# MINI_SAM_D51_009.net
KiCad netlist of a schematic drawn in EAGLE
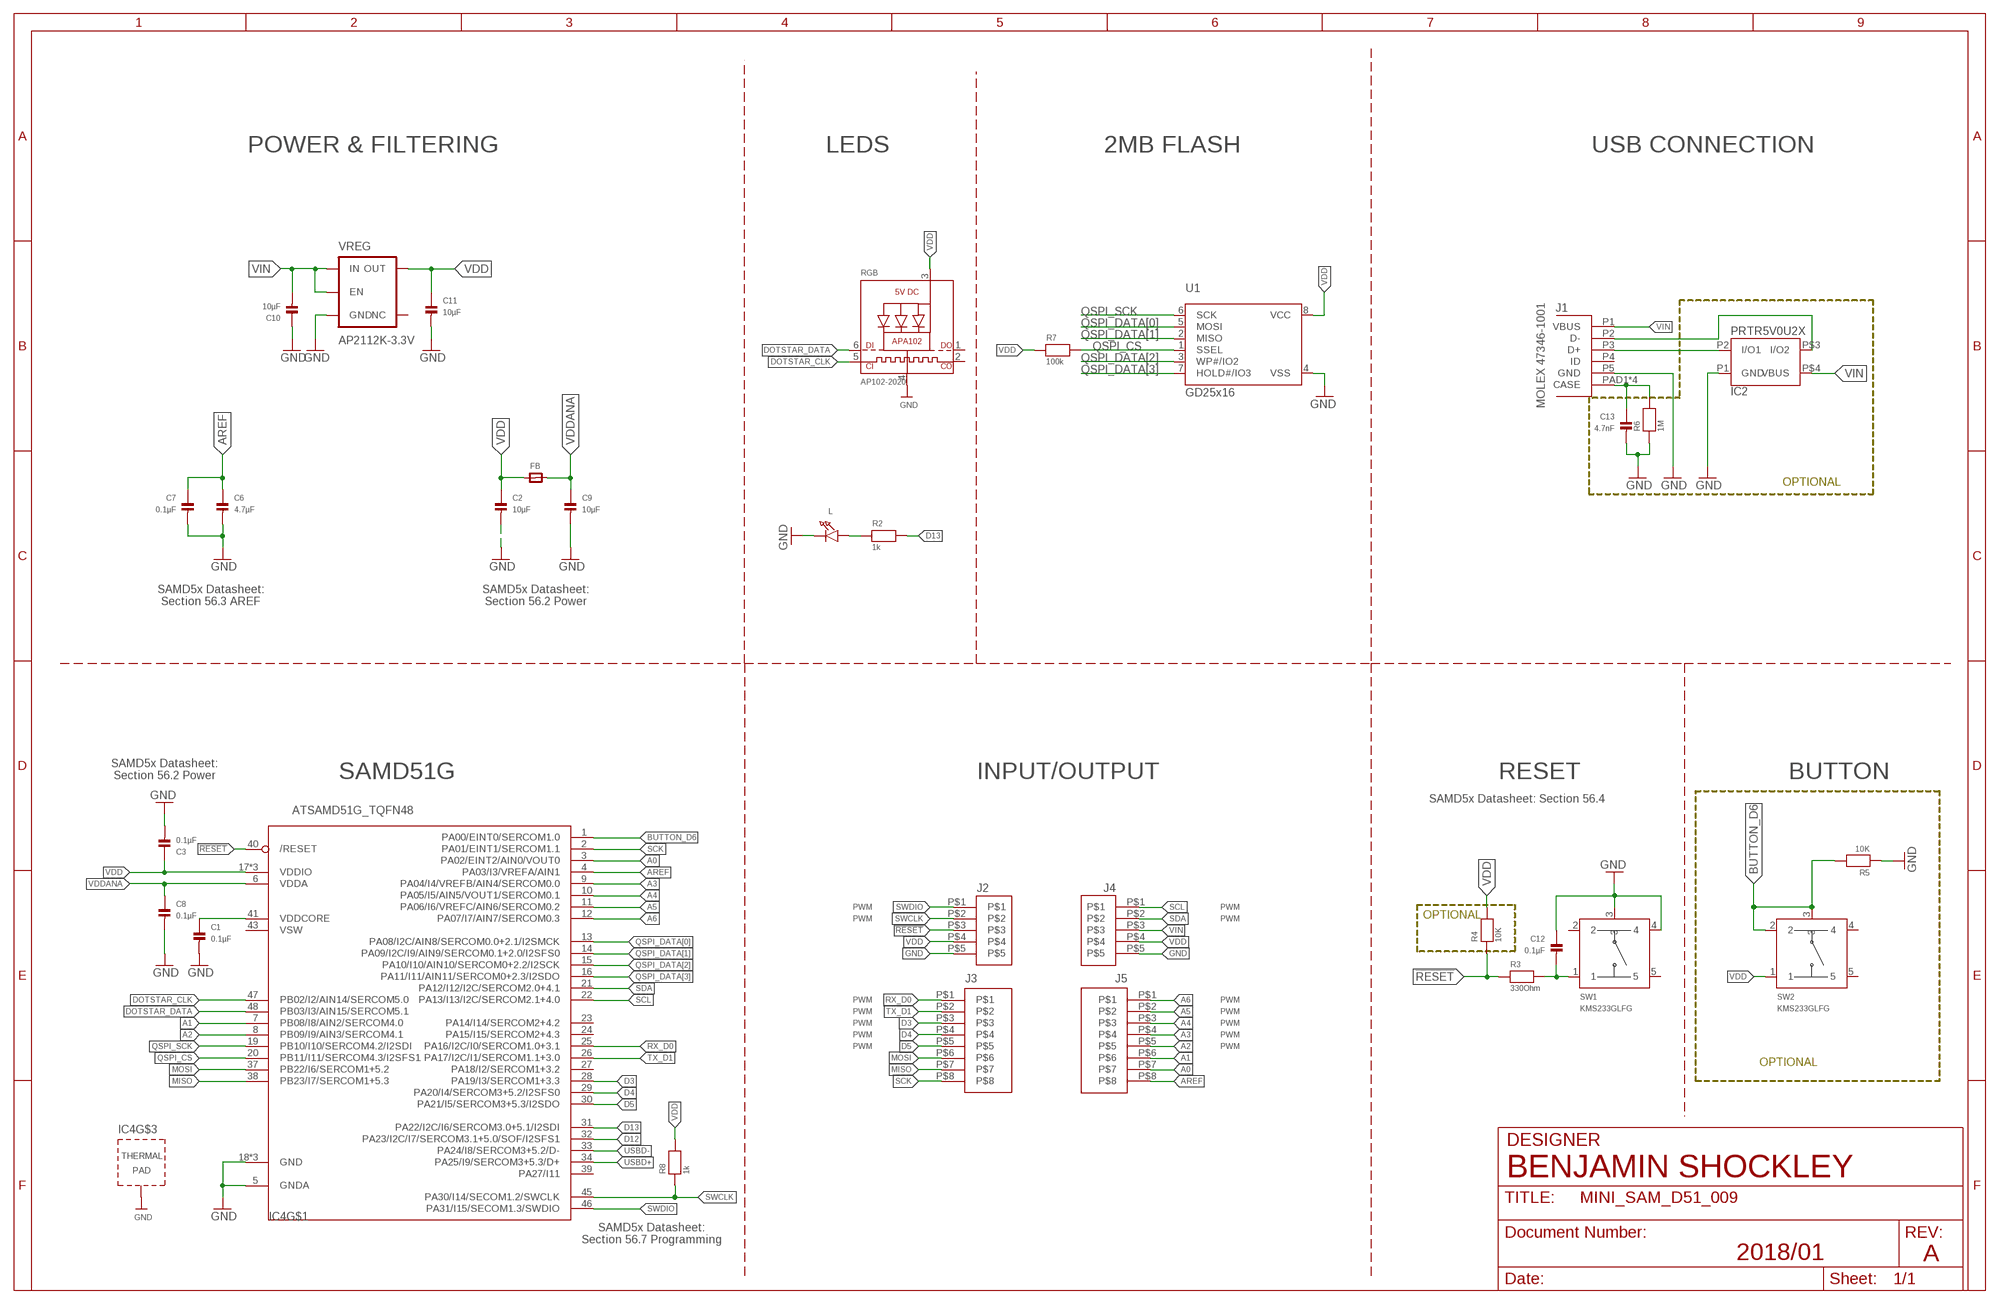
[diagram p0: schematic, sheet 1]

(export (version "E")
  (design (tool "Eeschema 10.0.6"))
  (components
    (comp (ref "C1")
      (value "0.1µF")
      (footprint "eagle-import:_0603MP")
      (libsource (lib "eagle-import") (part "CAP_CERAMIC_0603MP"))
    )
    (comp (ref "C2")
      (value "10µF")
      (footprint "eagle-import:_0603MP")
      (libsource (lib "eagle-import") (part "CAP_CERAMIC_0603MP"))
    )
    (comp (ref "C3")
      (value "0.1µF")
      (footprint "eagle-import:_0603MP")
      (libsource (lib "eagle-import") (part "CAP_CERAMIC_0603MP"))
    )
    (comp (ref "C6")
      (value "4.7µF")
      (footprint "eagle-import:_0603MP")
      (libsource (lib "eagle-import") (part "CAP_CERAMIC_0603MP"))
    )
    (comp (ref "C7")
      (value "0.1µF")
      (footprint "eagle-import:_0603MP")
      (libsource (lib "eagle-import") (part "CAP_CERAMIC_0603MP"))
    )
    (comp (ref "C8")
      (value "0.1µF")
      (footprint "eagle-import:_0603MP")
      (libsource (lib "eagle-import") (part "CAP_CERAMIC_0603MP"))
    )
    (comp (ref "C9")
      (value "10µF")
      (footprint "eagle-import:_0603MP")
      (libsource (lib "eagle-import") (part "CAP_CERAMIC_0603MP"))
    )
    (comp (ref "C10")
      (value "10µF")
      (footprint "eagle-import:_0603MP")
      (libsource (lib "eagle-import") (part "CAP_CERAMIC_0603MP"))
    )
    (comp (ref "C11")
      (value "10µF")
      (footprint "eagle-import:_0603MP")
      (libsource (lib "eagle-import") (part "CAP_CERAMIC_0603MP"))
    )
    (comp (ref "C12")
      (value "0.1µF")
      (footprint "eagle-import:_0603MP")
      (libsource (lib "eagle-import") (part "CAP_CERAMIC_0603MP"))
    )
    (comp (ref "C13")
      (value "4.7nF")
      (footprint "eagle-import:_0603MP")
      (libsource (lib "eagle-import") (part "CAP_CERAMIC_0603MP"))
    )
    (comp (ref "FB")
      (value "FERRITE_0603MP")
      (footprint "eagle-import:_0603MP")
      (libsource (lib "eagle-import") (part "FERRITE_0603MP"))
    )
    (comp (ref "IC2")
      (value "PRTR5V0U2X")
      (footprint "eagle-import:SOT143B_REFLOW")
      (libsource (lib "eagle-import") (part "PRTR5V0U2X"))
    )
    (comp (ref "IC4")
      (value "ATSAMD51G_TQFN48")
      (footprint "eagle-import:TQFN48_7MM")
      (libsource (lib "eagle-import") (part "ATSAMD51G_TQFN48"))
    )
    (comp (ref "J1")
      (value "MOLEX_47346-100147346")
      (footprint "eagle-import:MOLEX_47346-1001")
      (libsource (lib "eagle-import") (part "MOLEX_47346-100147346"))
    )
    (comp (ref "J2")
      (value "1X5_HEADER_1.27MM")
      (footprint "eagle-import:1X5_HEADER_1.27MM")
      (libsource (lib "eagle-import") (part "1X5_HEADER_1.27MM"))
    )
    (comp (ref "J3")
      (value "1X8_HEADER_1.27MM")
      (footprint "eagle-import:1X8_HEADER_1.27MM")
      (libsource (lib "eagle-import") (part "1X8_HEADER_1.27MM"))
    )
    (comp (ref "J4")
      (value "1X5_HEADER_1.27MM")
      (footprint "eagle-import:1X5_HEADER_1.27MM")
      (libsource (lib "eagle-import") (part "1X5_HEADER_1.27MM"))
    )
    (comp (ref "J5")
      (value "1X8_HEADER_1.27MM")
      (footprint "eagle-import:1X8_HEADER_1.27MM")
      (libsource (lib "eagle-import") (part "1X8_HEADER_1.27MM"))
    )
    (comp (ref "L")
      (value "LED0603_NOOUTLINE")
      (footprint "eagle-import:CHIPLED_0603_NOOUTLINE")
      (libsource (lib "eagle-import") (part "LED0603_NOOUTLINE"))
    )
    (comp (ref "R2")
      (value "1k")
      (footprint "eagle-import:_0603MP")
      (libsource (lib "eagle-import") (part "RESISTOR_0603MP"))
    )
    (comp (ref "R3")
      (value "330Ohm")
      (footprint "eagle-import:_0603MP")
      (libsource (lib "eagle-import") (part "RESISTOR_0603MP"))
    )
    (comp (ref "R4")
      (value "10K")
      (footprint "eagle-import:_0603MP")
      (libsource (lib "eagle-import") (part "RESISTOR_0603MP"))
    )
    (comp (ref "R5")
      (value "10K")
      (footprint "eagle-import:_0603MP")
      (libsource (lib "eagle-import") (part "RESISTOR_0603MP"))
    )
    (comp (ref "R6")
      (value "1M")
      (footprint "eagle-import:_0603MP")
      (libsource (lib "eagle-import") (part "RESISTOR_0603MP"))
    )
    (comp (ref "R7")
      (value "100k")
      (footprint "eagle-import:_0603MP")
      (libsource (lib "eagle-import") (part "RESISTOR_0603MP"))
    )
    (comp (ref "R8")
      (value "1k")
      (footprint "eagle-import:_0603MP")
      (libsource (lib "eagle-import") (part "RESISTOR_0603MP"))
    )
    (comp (ref "RGB")
      (value "AP102-2020")
      (footprint "eagle-import:APA102_2020")
      (libsource (lib "eagle-import") (part "APA1022020"))
    )
    (comp (ref "SW1")
      (value "KMS233GLFG")
      (footprint "eagle-import:KMS_SWITCH")
      (libsource (lib "eagle-import") (part "KMS_SWITCHKMS"))
    )
    (comp (ref "SW2")
      (value "KMS233GLFG")
      (footprint "eagle-import:KMS_SWITCH")
      (libsource (lib "eagle-import") (part "KMS_SWITCHKMS"))
    )
    (comp (ref "U1")
      (value "GD25x16")
      (footprint "eagle-import:USON8")
      (libsource (lib "eagle-import") (part "SPIFLASH_8PINUX"))
    )
    (comp (ref "VREG")
      (value "AP2112K-3.3V")
      (footprint "eagle-import:SOT23-5")
      (libsource (lib "eagle-import") (part "V_REG_AP2112K-3.3V"))
    )
  )
  (nets
    (net (code "1") (name "/VSW") (class "Default")
      (node (ref "IC4") (pin "43") (pinfunction "VSW_43") (pintype "power_in"))
    )
    (net (code "2") (name "/~{RESET}") (class "Default")
      (node (ref "IC4") (pin "40") (pinfunction "/RESET_40") (pintype "bidirectional"))
      (node (ref "J2") (pin "P$3") (pinfunction "P$3_P$3") (pintype "bidirectional"))
      (node (ref "R3") (pin "1") (pinfunction "1_1") (pintype "passive"))
      (node (ref "R4") (pin "1") (pinfunction "1_1") (pintype "passive"))
    )
    (net (code "3") (name "A0") (class "Default")
      (node (ref "IC4") (pin "3") (pinfunction "PA02/EINT2/AIN0/VOUT0_3") (pintype "bidirectional"))
      (node (ref "J5") (pin "P$7") (pinfunction "P$7_P$7") (pintype "bidirectional"))
    )
    (net (code "4") (name "A1") (class "Default")
      (node (ref "IC4") (pin "7") (pinfunction "PB08/I8/AIN2/SERCOM4.0_7") (pintype "bidirectional"))
      (node (ref "J5") (pin "P$6") (pinfunction "P$6_P$6") (pintype "bidirectional"))
    )
    (net (code "5") (name "A2") (class "Default")
      (node (ref "IC4") (pin "8") (pinfunction "PB09/I9/AIN3/SERCOM4.1_8") (pintype "bidirectional"))
      (node (ref "J5") (pin "P$5") (pinfunction "P$5_P$5") (pintype "bidirectional"))
    )
    (net (code "6") (name "A3") (class "Default")
      (node (ref "IC4") (pin "9") (pinfunction "PA04/I4/VREFB/AIN4/SERCOM0.0_9") (pintype "bidirectional"))
      (node (ref "J5") (pin "P$4") (pinfunction "P$4_P$4") (pintype "bidirectional"))
    )
    (net (code "7") (name "A4") (class "Default")
      (node (ref "IC4") (pin "10") (pinfunction "PA05/I5/AIN5/VOUT1/SERCOM0.1_10") (pintype "bidirectional"))
      (node (ref "J5") (pin "P$3") (pinfunction "P$3_P$3") (pintype "bidirectional"))
    )
    (net (code "8") (name "A5") (class "Default")
      (node (ref "IC4") (pin "11") (pinfunction "PA06/I6/VREFC/AIN6/SERCOM0.2_11") (pintype "bidirectional"))
      (node (ref "J5") (pin "P$2") (pinfunction "P$2_P$2") (pintype "bidirectional"))
    )
    (net (code "9") (name "A6") (class "Default")
      (node (ref "IC4") (pin "12") (pinfunction "PA07/I7/AIN7/SERCOM0.3_12") (pintype "bidirectional"))
      (node (ref "J5") (pin "P$1") (pinfunction "P$1_P$1") (pintype "bidirectional"))
    )
    (net (code "10") (name "AREF") (class "Default")
      (node (ref "C6") (pin "1") (pinfunction "P$1_1") (pintype "passive"))
      (node (ref "C7") (pin "1") (pinfunction "P$1_1") (pintype "passive"))
      (node (ref "IC4") (pin "4") (pinfunction "PA03/I3/VREFA/AIN1_4") (pintype "bidirectional"))
      (node (ref "J5") (pin "P$8") (pinfunction "P$8_P$8") (pintype "bidirectional"))
    )
    (net (code "11") (name "BUTTON_D6") (class "Default")
      (node (ref "IC4") (pin "1") (pinfunction "PA00/EINT0/SERCOM1.0_1") (pintype "bidirectional"))
      (node (ref "R5") (pin "2") (pinfunction "2_2") (pintype "passive"))
      (node (ref "SW2") (pin "2") (pinfunction "2_2") (pintype "bidirectional"))
      (node (ref "SW2") (pin "3") (pinfunction "3_3") (pintype "bidirectional"))
    )
    (net (code "12") (name "D3") (class "Default")
      (node (ref "IC4") (pin "28") (pinfunction "PA19/I3/SERCOM1+3.3_28") (pintype "bidirectional"))
      (node (ref "J3") (pin "P$3") (pinfunction "P$3_P$3") (pintype "bidirectional"))
    )
    (net (code "13") (name "D4") (class "Default")
      (node (ref "IC4") (pin "29") (pinfunction "PA20/I4/SERCOM3+5.2/I2SFS0_29") (pintype "bidirectional"))
      (node (ref "J3") (pin "P$4") (pinfunction "P$4_P$4") (pintype "bidirectional"))
    )
    (net (code "14") (name "D5") (class "Default")
      (node (ref "IC4") (pin "30") (pinfunction "PA21/I5/SERCOM3+5.3/I2SDO_30") (pintype "bidirectional"))
      (node (ref "J3") (pin "P$5") (pinfunction "P$5_P$5") (pintype "bidirectional"))
    )
    (net (code "15") (name "D12") (class "Default")
      (node (ref "IC4") (pin "32") (pinfunction "PA23/I2C/I7/SERCOM3.1+5.0/SOF/I2SFS1_32") (pintype "bidirectional"))
    )
    (net (code "16") (name "D13") (class "Default")
      (node (ref "IC4") (pin "31") (pinfunction "PA22/I2C/I6/SERCOM3.0+5.1/I2SDI_31") (pintype "bidirectional"))
      (node (ref "R2") (pin "2") (pinfunction "2_2") (pintype "passive"))
    )
    (net (code "17") (name "DOTSTAR_CLK") (class "Default")
      (node (ref "IC4") (pin "47") (pinfunction "PB02/I2/AIN14/SERCOM5.0_47") (pintype "bidirectional"))
      (node (ref "RGB") (pin "5") (pinfunction "CKI_5") (pintype "input"))
    )
    (net (code "18") (name "DOTSTAR_DATA") (class "Default")
      (node (ref "IC4") (pin "48") (pinfunction "PB03/I3/AIN15/SERCOM5.1_48") (pintype "bidirectional"))
      (node (ref "RGB") (pin "6") (pinfunction "DI_6") (pintype "input"))
    )
    (net (code "19") (name "GND") (class "Default")
      (node (ref "C1") (pin "2") (pinfunction "P$2_2") (pintype "passive"))
      (node (ref "C10") (pin "1") (pinfunction "P$1_1") (pintype "passive"))
      (node (ref "C11") (pin "2") (pinfunction "P$2_2") (pintype "passive"))
      (node (ref "C12") (pin "1") (pinfunction "P$1_1") (pintype "passive"))
      (node (ref "C13") (pin "2") (pinfunction "P$2_2") (pintype "passive"))
      (node (ref "C2") (pin "2") (pinfunction "P$2_2") (pintype "passive"))
      (node (ref "C3") (pin "2") (pinfunction "P$2_2") (pintype "passive"))
      (node (ref "C6") (pin "2") (pinfunction "P$2_2") (pintype "passive"))
      (node (ref "C7") (pin "2") (pinfunction "P$2_2") (pintype "passive"))
      (node (ref "C8") (pin "2") (pinfunction "P$2_2") (pintype "passive"))
      (node (ref "C9") (pin "2") (pinfunction "P$2_2") (pintype "passive"))
      (node (ref "IC2") (pin "P1") (pinfunction "GND_P1") (pintype "bidirectional"))
      (node (ref "IC4") (pin "18") (pinfunction "GND_18") (pintype "power_in"))
      (node (ref "IC4") (pin "35") (pinfunction "GND_35") (pintype "power_in"))
      (node (ref "IC4") (pin "42") (pinfunction "GND_42") (pintype "power_in"))
      (node (ref "IC4") (pin "5") (pinfunction "GNDA_5") (pintype "power_in"))
      (node (ref "IC4") (pin "THERMAL") (pinfunction "TP_THERMAL") (pintype "power_in"))
      (node (ref "J1") (pin "P5") (pinfunction "GND_P5") (pintype "power_in"))
      (node (ref "J2") (pin "P$5") (pinfunction "P$5_P$5") (pintype "bidirectional"))
      (node (ref "J4") (pin "P$5") (pinfunction "P$5_P$5") (pintype "bidirectional"))
      (node (ref "L") (pin "C") (pinfunction "C_C") (pintype "passive"))
      (node (ref "R5") (pin "1") (pinfunction "1_1") (pintype "passive"))
      (node (ref "R6") (pin "1") (pinfunction "1_1") (pintype "passive"))
      (node (ref "RGB") (pin "4") (pinfunction "GND_4") (pintype "power_in"))
      (node (ref "SW1") (pin "3") (pinfunction "3_3") (pintype "bidirectional"))
      (node (ref "SW1") (pin "4") (pinfunction "4_4") (pintype "bidirectional"))
      (node (ref "U1") (pin "4") (pinfunction "VSS_4") (pintype "bidirectional"))
      (node (ref "VREG") (pin "2") (pinfunction "GND_2") (pintype "input"))
    )
    (net (code "20") (name "MISO") (class "Default")
      (node (ref "IC4") (pin "38") (pinfunction "PB23/I7/SERCOM1+5.3_38") (pintype "bidirectional"))
      (node (ref "J3") (pin "P$7") (pinfunction "P$7_P$7") (pintype "bidirectional"))
    )
    (net (code "21") (name "MOSI") (class "Default")
      (node (ref "IC4") (pin "37") (pinfunction "PB22/I6/SERCOM1+5.2_37") (pintype "bidirectional"))
      (node (ref "J3") (pin "P$6") (pinfunction "P$6_P$6") (pintype "bidirectional"))
    )
    (net (code "22") (name "Net-(C1-P$1)") (class "Default")
      (node (ref "C1") (pin "1") (pinfunction "P$1_1") (pintype "passive"))
      (node (ref "IC4") (pin "41") (pinfunction "VDDCORE_41") (pintype "power_in"))
    )
    (net (code "23") (name "Net-(C12-P$2)") (class "Default")
      (node (ref "C12") (pin "2") (pinfunction "P$2_2") (pintype "passive"))
      (node (ref "R3") (pin "2") (pinfunction "2_2") (pintype "passive"))
      (node (ref "SW1") (pin "1") (pinfunction "1_1") (pintype "bidirectional"))
    )
    (net (code "24") (name "Net-(C13-P$1)") (class "Default")
      (node (ref "C13") (pin "1") (pinfunction "P$1_1") (pintype "passive"))
      (node (ref "J1") (pin "PAD1") (pinfunction "CASE_PAD1") (pintype "bidirectional"))
      (node (ref "J1") (pin "PAD2") (pinfunction "CASE_PAD2") (pintype "bidirectional"))
      (node (ref "J1") (pin "PAD3") (pinfunction "CASE_PAD3") (pintype "bidirectional"))
      (node (ref "J1") (pin "PAD4") (pinfunction "CASE_PAD4") (pintype "bidirectional"))
      (node (ref "R6") (pin "2") (pinfunction "2_2") (pintype "passive"))
    )
    (net (code "25") (name "Net-(L-PadA)") (class "Default")
      (node (ref "L") (pin "A") (pinfunction "A_A") (pintype "passive"))
      (node (ref "R2") (pin "1") (pinfunction "1_1") (pintype "passive"))
    )
    (net (code "26") (name "QSPI_CS") (class "Default")
      (node (ref "IC4") (pin "20") (pinfunction "PB11/I11/SERCOM4.3/I2SFS1_20") (pintype "bidirectional"))
      (node (ref "R7") (pin "2") (pinfunction "2_2") (pintype "passive"))
      (node (ref "U1") (pin "1") (pinfunction "SSEL_1") (pintype "bidirectional"))
    )
    (net (code "27") (name "QSPI_DATA[0]") (class "Default")
      (node (ref "IC4") (pin "13") (pinfunction "PA08/I2C/AIN8/SERCOM0.0+2.1/I2SMCK_13") (pintype "bidirectional"))
      (node (ref "U1") (pin "5") (pinfunction "MOSI_5") (pintype "bidirectional"))
    )
    (net (code "28") (name "QSPI_DATA[1]") (class "Default")
      (node (ref "IC4") (pin "14") (pinfunction "PA09/I2C/I9/AIN9/SERCOM0.1+2.0/I2SFS0_14") (pintype "bidirectional"))
      (node (ref "U1") (pin "2") (pinfunction "MISO_2") (pintype "bidirectional"))
    )
    (net (code "29") (name "QSPI_DATA[2]") (class "Default")
      (node (ref "IC4") (pin "15") (pinfunction "PA10/I10/AIN10/SERCOM0+2.2/I2SCK_15") (pintype "bidirectional"))
      (node (ref "U1") (pin "3") (pinfunction "WP#/IO2_3") (pintype "bidirectional"))
    )
    (net (code "30") (name "QSPI_DATA[3]") (class "Default")
      (node (ref "IC4") (pin "16") (pinfunction "PA11/I11/AIN11/SERCOM0+2.3/I2SDO_16") (pintype "bidirectional"))
      (node (ref "U1") (pin "7") (pinfunction "HOLD#/IO3_7") (pintype "bidirectional"))
    )
    (net (code "31") (name "QSPI_SCK") (class "Default")
      (node (ref "IC4") (pin "19") (pinfunction "PB10/I10/SERCOM4.2/I2SDI_19") (pintype "bidirectional"))
      (node (ref "U1") (pin "6") (pinfunction "SCK_6") (pintype "bidirectional"))
    )
    (net (code "32") (name "RX_D0") (class "Default")
      (node (ref "IC4") (pin "25") (pinfunction "PA16/I2C/I0/SERCOM1.0+3.1_25") (pintype "bidirectional"))
      (node (ref "J3") (pin "P$1") (pinfunction "P$1_P$1") (pintype "bidirectional"))
    )
    (net (code "33") (name "SCK") (class "Default")
      (node (ref "IC4") (pin "2") (pinfunction "PA01/EINT1/SERCOM1.1_2") (pintype "bidirectional"))
      (node (ref "J3") (pin "P$8") (pinfunction "P$8_P$8") (pintype "bidirectional"))
    )
    (net (code "34") (name "SCL") (class "Default")
      (node (ref "IC4") (pin "22") (pinfunction "PA13/I13/I2C/SERCOM2.1+4.0_22") (pintype "bidirectional"))
      (node (ref "J4") (pin "P$1") (pinfunction "P$1_P$1") (pintype "bidirectional"))
    )
    (net (code "35") (name "SDA") (class "Default")
      (node (ref "IC4") (pin "21") (pinfunction "PA12/I12/I2C/SERCOM2.0+4.1_21") (pintype "bidirectional"))
      (node (ref "J4") (pin "P$2") (pinfunction "P$2_P$2") (pintype "bidirectional"))
    )
    (net (code "36") (name "SWCLK") (class "Default")
      (node (ref "IC4") (pin "45") (pinfunction "PA30/I14/SECOM1.2/SWCLK_45") (pintype "bidirectional"))
      (node (ref "J2") (pin "P$2") (pinfunction "P$2_P$2") (pintype "bidirectional"))
      (node (ref "R8") (pin "1") (pinfunction "1_1") (pintype "passive"))
    )
    (net (code "37") (name "SWDIO") (class "Default")
      (node (ref "IC4") (pin "46") (pinfunction "PA31/I15/SECOM1.3/SWDIO_46") (pintype "bidirectional"))
      (node (ref "J2") (pin "P$1") (pinfunction "P$1_P$1") (pintype "bidirectional"))
    )
    (net (code "38") (name "TX_D1") (class "Default")
      (node (ref "IC4") (pin "26") (pinfunction "PA17/I2C/I1/SERCOM1.1+3.0_26") (pintype "bidirectional"))
      (node (ref "J3") (pin "P$2") (pinfunction "P$2_P$2") (pintype "bidirectional"))
    )
    (net (code "39") (name "USBD+") (class "Default")
      (node (ref "IC2") (pin "P2") (pinfunction "I/O1_P2") (pintype "bidirectional"))
      (node (ref "IC4") (pin "34") (pinfunction "PA25/I9/SERCOM3+5.3/D+_34") (pintype "bidirectional"))
      (node (ref "J1") (pin "P3") (pinfunction "D+_P3") (pintype "bidirectional"))
    )
    (net (code "40") (name "USBD-") (class "Default")
      (node (ref "IC2") (pin "P$3") (pinfunction "I/O2_P$3") (pintype "bidirectional"))
      (node (ref "IC4") (pin "33") (pinfunction "PA24/I8/SERCOM3+5.2/D-_33") (pintype "bidirectional"))
      (node (ref "J1") (pin "P2") (pinfunction "D-_P2") (pintype "bidirectional"))
    )
    (net (code "41") (name "VDD") (class "Default")
      (node (ref "C11") (pin "1") (pinfunction "P$1_1") (pintype "passive"))
      (node (ref "C2") (pin "1") (pinfunction "P$1_1") (pintype "passive"))
      (node (ref "C3") (pin "1") (pinfunction "P$1_1") (pintype "passive"))
      (node (ref "FB") (pin "1") (pinfunction "P$1_1") (pintype "passive"))
      (node (ref "IC4") (pin "17") (pinfunction "VDDIO_17") (pintype "power_in"))
      (node (ref "IC4") (pin "36") (pinfunction "VDDIO_36") (pintype "power_in"))
      (node (ref "IC4") (pin "44") (pinfunction "VDDIO_44") (pintype "power_in"))
      (node (ref "J2") (pin "P$4") (pinfunction "P$4_P$4") (pintype "bidirectional"))
      (node (ref "J4") (pin "P$4") (pinfunction "P$4_P$4") (pintype "bidirectional"))
      (node (ref "R4") (pin "2") (pinfunction "2_2") (pintype "passive"))
      (node (ref "R7") (pin "1") (pinfunction "1_1") (pintype "passive"))
      (node (ref "R8") (pin "2") (pinfunction "2_2") (pintype "passive"))
      (node (ref "RGB") (pin "3") (pinfunction "VDD_3") (pintype "power_in"))
      (node (ref "SW2") (pin "1") (pinfunction "1_1") (pintype "bidirectional"))
      (node (ref "U1") (pin "8") (pinfunction "VCC_8") (pintype "bidirectional"))
      (node (ref "VREG") (pin "5") (pinfunction "OUT_5") (pintype "passive"))
    )
    (net (code "42") (name "VDDANA") (class "Default")
      (node (ref "C8") (pin "1") (pinfunction "P$1_1") (pintype "passive"))
      (node (ref "C9") (pin "1") (pinfunction "P$1_1") (pintype "passive"))
      (node (ref "FB") (pin "2") (pinfunction "P$2_2") (pintype "passive"))
      (node (ref "IC4") (pin "6") (pinfunction "VDDA_6") (pintype "power_in"))
    )
    (net (code "43") (name "VIN") (class "Default")
      (node (ref "C10") (pin "2") (pinfunction "P$2_2") (pintype "passive"))
      (node (ref "IC2") (pin "P$4") (pinfunction "VBUS_P$4") (pintype "bidirectional"))
      (node (ref "J1") (pin "P1") (pinfunction "VBUS_P1") (pintype "power_in"))
      (node (ref "J4") (pin "P$3") (pinfunction "P$3_P$3") (pintype "bidirectional"))
      (node (ref "VREG") (pin "1") (pinfunction "IN_1") (pintype "input"))
      (node (ref "VREG") (pin "3") (pinfunction "EN_3") (pintype "input"))
    )
    (net (code "44") (name "unconnected-(IC4A-PA14{slash}I14{slash}SERCOM2+4.2-Pad23)") (class "Default")
      (node (ref "IC4") (pin "23") (pinfunction "PA14/I14/SERCOM2+4.2_23") (pintype "bidirectional"))
    )
    (net (code "45") (name "unconnected-(IC4A-PA15{slash}I15{slash}SERCOM2+4.3-Pad24)") (class "Default")
      (node (ref "IC4") (pin "24") (pinfunction "PA15/I15/SERCOM2+4.3_24") (pintype "bidirectional"))
    )
    (net (code "46") (name "unconnected-(IC4A-PA18{slash}I2{slash}SERCOM1+3.2-Pad27)") (class "Default")
      (node (ref "IC4") (pin "27") (pinfunction "PA18/I2/SERCOM1+3.2_27") (pintype "bidirectional"))
    )
    (net (code "47") (name "unconnected-(IC4A-PA27{slash}I11-Pad39)") (class "Default")
      (node (ref "IC4") (pin "39") (pinfunction "PA27/I11_39") (pintype "bidirectional"))
    )
    (net (code "48") (name "unconnected-(J1-ID-PadP4)") (class "Default")
      (node (ref "J1") (pin "P4") (pinfunction "ID_P4") (pintype "bidirectional"))
    )
    (net (code "49") (name "unconnected-(RGB-CKO-Pad2)") (class "Default")
      (node (ref "RGB") (pin "2") (pinfunction "CKO_2") (pintype "output"))
    )
    (net (code "50") (name "unconnected-(RGB-DO-Pad1)") (class "Default")
      (node (ref "RGB") (pin "1") (pinfunction "DO_1") (pintype "output"))
    )
    (net (code "51") (name "unconnected-(SW1-Pad2)") (class "Default")
      (node (ref "SW1") (pin "2") (pinfunction "2_2") (pintype "bidirectional"))
    )
    (net (code "52") (name "unconnected-(SW1-Pad5)") (class "Default")
      (node (ref "SW1") (pin "5") (pinfunction "5_5") (pintype "bidirectional"))
    )
    (net (code "53") (name "unconnected-(SW2-Pad4)") (class "Default")
      (node (ref "SW2") (pin "4") (pinfunction "4_4") (pintype "bidirectional"))
    )
    (net (code "54") (name "unconnected-(SW2-Pad5)") (class "Default")
      (node (ref "SW2") (pin "5") (pinfunction "5_5") (pintype "bidirectional"))
    )
    (net (code "55") (name "unconnected-(VREG-NC-Pad4)") (class "Default")
      (node (ref "VREG") (pin "4") (pinfunction "NC_4") (pintype "input"))
    )
  )
)
